# SCH_SpotiFi_2026-06-15.net
KiCad netlist of a schematic drawn in EasyEDA
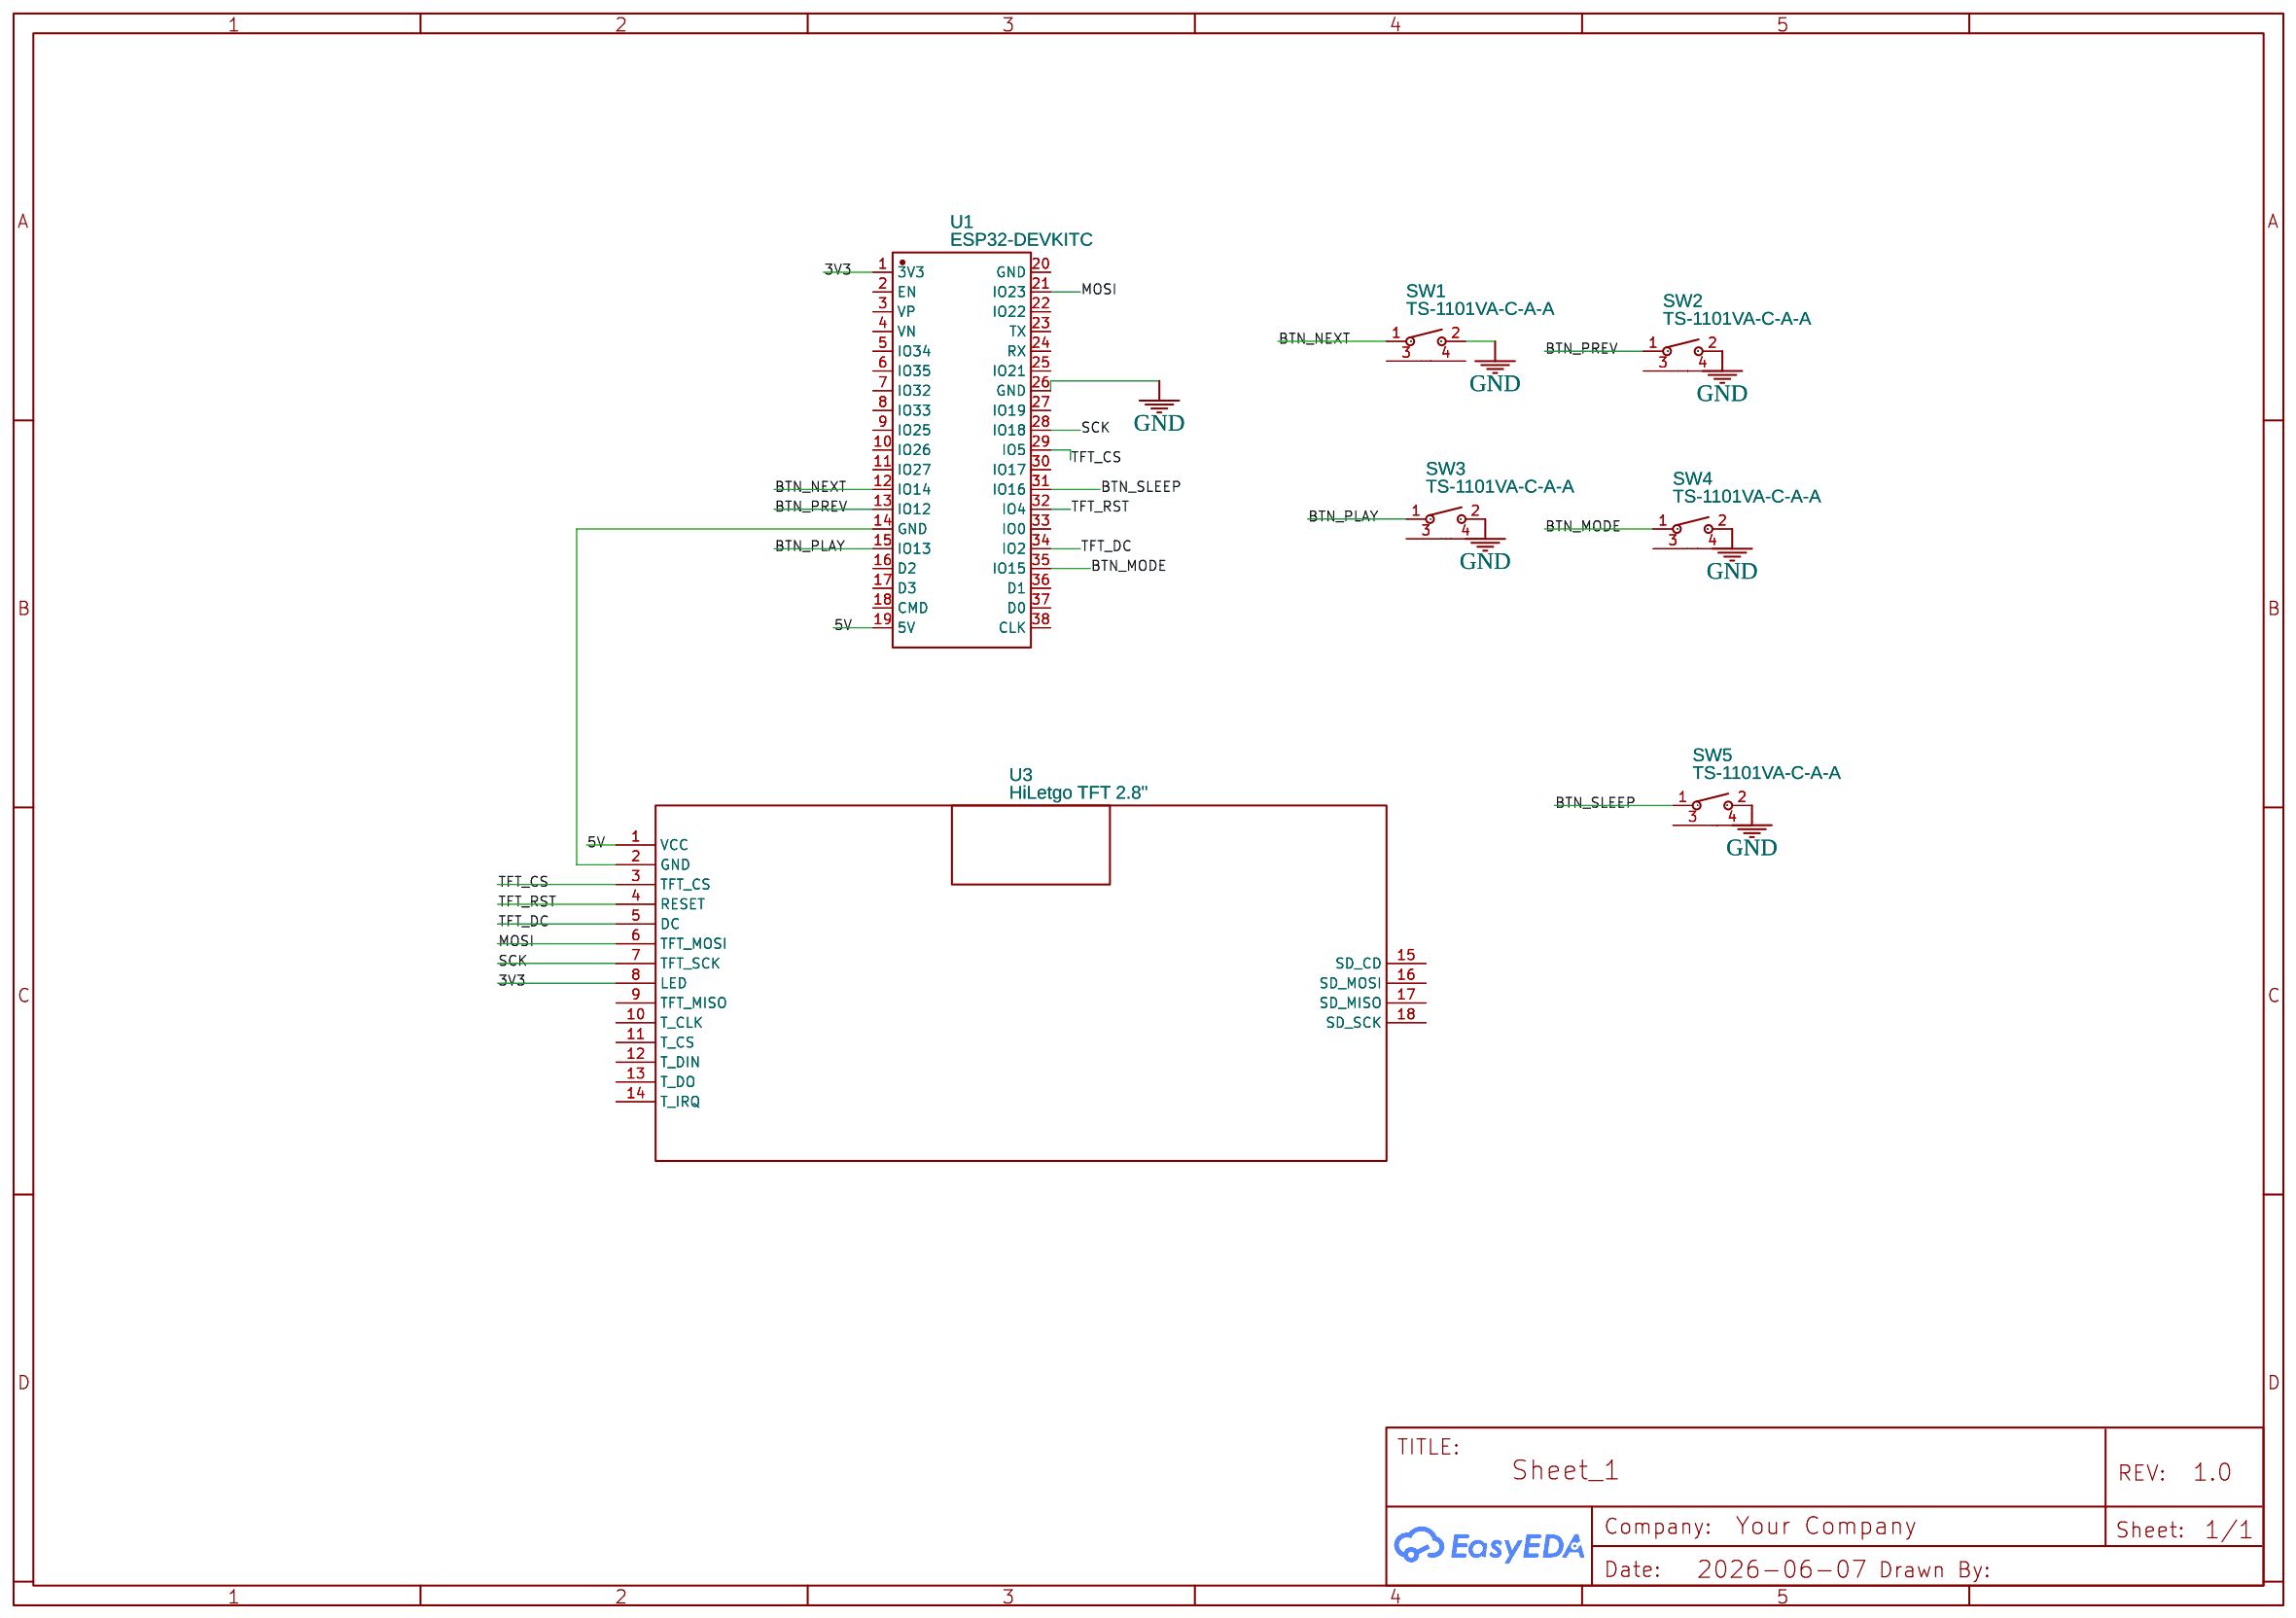
[diagram p0: schematic sheet]

(export (version "E")
  (design (tool "Eeschema 10.0.6"))
  (components
    (comp (ref "SW1")
      (value "TS-1101VA-C-A-A")
      (fields (field (name "Manufacturer") "XKB Connection(中国星坤)"))
      (libsource (lib "") (part "TS-1101VA-C-A-A"))
    )
    (comp (ref "SW2")
      (value "TS-1101VA-C-A-A")
      (fields (field (name "Manufacturer") "XKB Connection(中国星坤)"))
      (libsource (lib "") (part "TS-1101VA-C-A-A"))
    )
    (comp (ref "SW3")
      (value "TS-1101VA-C-A-A")
      (fields (field (name "Manufacturer") "XKB Connection(中国星坤)"))
      (libsource (lib "") (part "TS-1101VA-C-A-A"))
    )
    (comp (ref "SW4")
      (value "TS-1101VA-C-A-A")
      (fields (field (name "Manufacturer") "XKB Connection(中国星坤)"))
      (libsource (lib "") (part "TS-1101VA-C-A-A"))
    )
    (comp (ref "SW5")
      (value "TS-1101VA-C-A-A")
      (fields (field (name "Manufacturer") "XKB Connection(中国星坤)"))
      (libsource (lib "") (part "TS-1101VA-C-A-A"))
    )
    (comp (ref "U1")
      (value "ESP32-DEVKITC")
      (fields
        (field (name "Manufacturer Part") "ESP32-DevKitC")
        (field (name "Manufacturer") "ESPRESSIF(乐鑫)")
      )
      (libsource (lib "") (part "ESP32-DEVKITC"))
    )
    (comp (ref "U3") (value "HiLetgo TFT 2.8\"") (libsource (lib "") (part "HiLetgo TFT 2.8{dblquote}")))
  )
  (nets
    (net (code "1") (name "/3V3") (class "Default")
      (node (ref "U1") (pin "1") (pinfunction "3V3_1") (pintype "unspecified"))
      (node (ref "U3") (pin "8") (pinfunction "LED_8") (pintype "unspecified"))
    )
    (net (code "2") (name "/5V") (class "Default")
      (node (ref "U1") (pin "19") (pinfunction "5V_19") (pintype "unspecified"))
      (node (ref "U3") (pin "1") (pinfunction "VCC_1") (pintype "unspecified"))
    )
    (net (code "3") (name "/BTN_MODE") (class "Default")
      (node (ref "SW4") (pin "1") (pinfunction "1_1") (pintype "unspecified"))
      (node (ref "U1") (pin "35") (pinfunction "IO15_35") (pintype "unspecified"))
    )
    (net (code "4") (name "/BTN_NEXT") (class "Default")
      (node (ref "SW1") (pin "1") (pinfunction "1_1") (pintype "unspecified"))
      (node (ref "U1") (pin "12") (pinfunction "IO14_12") (pintype "unspecified"))
    )
    (net (code "5") (name "/BTN_PLAY") (class "Default")
      (node (ref "SW3") (pin "1") (pinfunction "1_1") (pintype "unspecified"))
      (node (ref "U1") (pin "15") (pinfunction "IO13_15") (pintype "unspecified"))
    )
    (net (code "6") (name "/BTN_PREV") (class "Default")
      (node (ref "SW2") (pin "1") (pinfunction "1_1") (pintype "unspecified"))
      (node (ref "U1") (pin "13") (pinfunction "IO12_13") (pintype "unspecified"))
    )
    (net (code "7") (name "/BTN_SLEEP") (class "Default")
      (node (ref "SW5") (pin "1") (pinfunction "1_1") (pintype "unspecified"))
      (node (ref "U1") (pin "31") (pinfunction "IO16_31") (pintype "unspecified"))
    )
    (net (code "8") (name "/MOSI") (class "Default")
      (node (ref "U1") (pin "21") (pinfunction "IO23_21") (pintype "unspecified"))
      (node (ref "U3") (pin "6") (pinfunction "TFT_MOSI_6") (pintype "unspecified"))
    )
    (net (code "9") (name "/SCK") (class "Default")
      (node (ref "U1") (pin "28") (pinfunction "IO18_28") (pintype "unspecified"))
      (node (ref "U3") (pin "7") (pinfunction "TFT_SCK_7") (pintype "unspecified"))
    )
    (net (code "10") (name "/TFT_CS") (class "Default")
      (node (ref "U1") (pin "29") (pinfunction "IO5_29") (pintype "unspecified"))
      (node (ref "U3") (pin "3") (pinfunction "TFT_CS_3") (pintype "unspecified"))
    )
    (net (code "11") (name "/TFT_DC") (class "Default")
      (node (ref "U1") (pin "34") (pinfunction "IO2_34") (pintype "unspecified"))
      (node (ref "U3") (pin "5") (pinfunction "DC_5") (pintype "unspecified"))
    )
    (net (code "12") (name "/TFT_RST") (class "Default")
      (node (ref "U1") (pin "32") (pinfunction "IO4_32") (pintype "unspecified"))
      (node (ref "U3") (pin "4") (pinfunction "RESET_4") (pintype "unspecified"))
    )
    (net (code "13") (name "GND") (class "Default")
      (node (ref "SW1") (pin "2") (pinfunction "2_2") (pintype "unspecified"))
      (node (ref "SW2") (pin "2") (pinfunction "2_2") (pintype "unspecified"))
      (node (ref "SW3") (pin "2") (pinfunction "2_2") (pintype "unspecified"))
      (node (ref "SW4") (pin "2") (pinfunction "2_2") (pintype "unspecified"))
      (node (ref "SW5") (pin "2") (pinfunction "2_2") (pintype "unspecified"))
      (node (ref "U1") (pin "26") (pinfunction "GND_26") (pintype "unspecified"))
    )
    (net (code "14") (name "Net-(U3-GND)") (class "Default")
      (node (ref "U1") (pin "14") (pinfunction "GND_14") (pintype "unspecified"))
      (node (ref "U3") (pin "2") (pinfunction "GND_2") (pintype "unspecified"))
    )
    (net (code "15") (name "unconnected-(SW1-Pad3)") (class "Default")
      (node (ref "SW1") (pin "3") (pinfunction "3_3") (pintype "unspecified"))
    )
    (net (code "16") (name "unconnected-(SW1-Pad4)") (class "Default")
      (node (ref "SW1") (pin "4") (pinfunction "4_4") (pintype "unspecified"))
    )
    (net (code "17") (name "unconnected-(SW2-Pad3)") (class "Default")
      (node (ref "SW2") (pin "3") (pinfunction "3_3") (pintype "unspecified"))
    )
    (net (code "18") (name "unconnected-(SW2-Pad4)") (class "Default")
      (node (ref "SW2") (pin "4") (pinfunction "4_4") (pintype "unspecified"))
    )
    (net (code "19") (name "unconnected-(SW3-Pad3)") (class "Default")
      (node (ref "SW3") (pin "3") (pinfunction "3_3") (pintype "unspecified"))
    )
    (net (code "20") (name "unconnected-(SW3-Pad4)") (class "Default")
      (node (ref "SW3") (pin "4") (pinfunction "4_4") (pintype "unspecified"))
    )
    (net (code "21") (name "unconnected-(SW4-Pad3)") (class "Default")
      (node (ref "SW4") (pin "3") (pinfunction "3_3") (pintype "unspecified"))
    )
    (net (code "22") (name "unconnected-(SW4-Pad4)") (class "Default")
      (node (ref "SW4") (pin "4") (pinfunction "4_4") (pintype "unspecified"))
    )
    (net (code "23") (name "unconnected-(SW5-Pad3)") (class "Default")
      (node (ref "SW5") (pin "3") (pinfunction "3_3") (pintype "unspecified"))
    )
    (net (code "24") (name "unconnected-(SW5-Pad4)") (class "Default")
      (node (ref "SW5") (pin "4") (pinfunction "4_4") (pintype "unspecified"))
    )
    (net (code "25") (name "unconnected-(U1-CLK-Pad38)") (class "Default")
      (node (ref "U1") (pin "38") (pinfunction "CLK_38") (pintype "unspecified"))
    )
    (net (code "26") (name "unconnected-(U1-CMD-Pad18)") (class "Default")
      (node (ref "U1") (pin "18") (pinfunction "CMD_18") (pintype "unspecified"))
    )
    (net (code "27") (name "unconnected-(U1-D0-Pad37)") (class "Default")
      (node (ref "U1") (pin "37") (pinfunction "D0_37") (pintype "unspecified"))
    )
    (net (code "28") (name "unconnected-(U1-D1-Pad36)") (class "Default")
      (node (ref "U1") (pin "36") (pinfunction "D1_36") (pintype "unspecified"))
    )
    (net (code "29") (name "unconnected-(U1-D2-Pad16)") (class "Default")
      (node (ref "U1") (pin "16") (pinfunction "D2_16") (pintype "unspecified"))
    )
    (net (code "30") (name "unconnected-(U1-D3-Pad17)") (class "Default")
      (node (ref "U1") (pin "17") (pinfunction "D3_17") (pintype "unspecified"))
    )
    (net (code "31") (name "unconnected-(U1-EN-Pad2)") (class "Default")
      (node (ref "U1") (pin "2") (pinfunction "EN_2") (pintype "unspecified"))
    )
    (net (code "32") (name "unconnected-(U1-GND-Pad20)") (class "Default")
      (node (ref "U1") (pin "20") (pinfunction "GND_20") (pintype "unspecified"))
    )
    (net (code "33") (name "unconnected-(U1-IO0-Pad33)") (class "Default")
      (node (ref "U1") (pin "33") (pinfunction "IO0_33") (pintype "unspecified"))
    )
    (net (code "34") (name "unconnected-(U1-IO17-Pad30)") (class "Default")
      (node (ref "U1") (pin "30") (pinfunction "IO17_30") (pintype "unspecified"))
    )
    (net (code "35") (name "unconnected-(U1-IO19-Pad27)") (class "Default")
      (node (ref "U1") (pin "27") (pinfunction "IO19_27") (pintype "unspecified"))
    )
    (net (code "36") (name "unconnected-(U1-IO21-Pad25)") (class "Default")
      (node (ref "U1") (pin "25") (pinfunction "IO21_25") (pintype "unspecified"))
    )
    (net (code "37") (name "unconnected-(U1-IO22-Pad22)") (class "Default")
      (node (ref "U1") (pin "22") (pinfunction "IO22_22") (pintype "unspecified"))
    )
    (net (code "38") (name "unconnected-(U1-IO25-Pad9)") (class "Default")
      (node (ref "U1") (pin "9") (pinfunction "IO25_9") (pintype "unspecified"))
    )
    (net (code "39") (name "unconnected-(U1-IO26-Pad10)") (class "Default")
      (node (ref "U1") (pin "10") (pinfunction "IO26_10") (pintype "unspecified"))
    )
    (net (code "40") (name "unconnected-(U1-IO27-Pad11)") (class "Default")
      (node (ref "U1") (pin "11") (pinfunction "IO27_11") (pintype "unspecified"))
    )
    (net (code "41") (name "unconnected-(U1-IO32-Pad7)") (class "Default")
      (node (ref "U1") (pin "7") (pinfunction "IO32_7") (pintype "unspecified"))
    )
    (net (code "42") (name "unconnected-(U1-IO33-Pad8)") (class "Default")
      (node (ref "U1") (pin "8") (pinfunction "IO33_8") (pintype "unspecified"))
    )
    (net (code "43") (name "unconnected-(U1-IO34-Pad5)") (class "Default")
      (node (ref "U1") (pin "5") (pinfunction "IO34_5") (pintype "unspecified"))
    )
    (net (code "44") (name "unconnected-(U1-IO35-Pad6)") (class "Default")
      (node (ref "U1") (pin "6") (pinfunction "IO35_6") (pintype "unspecified"))
    )
    (net (code "45") (name "unconnected-(U1-RX-Pad24)") (class "Default")
      (node (ref "U1") (pin "24") (pinfunction "RX_24") (pintype "unspecified"))
    )
    (net (code "46") (name "unconnected-(U1-TX-Pad23)") (class "Default")
      (node (ref "U1") (pin "23") (pinfunction "TX_23") (pintype "unspecified"))
    )
    (net (code "47") (name "unconnected-(U1-VN-Pad4)") (class "Default")
      (node (ref "U1") (pin "4") (pinfunction "VN_4") (pintype "unspecified"))
    )
    (net (code "48") (name "unconnected-(U1-VP-Pad3)") (class "Default")
      (node (ref "U1") (pin "3") (pinfunction "VP_3") (pintype "unspecified"))
    )
    (net (code "49") (name "unconnected-(U3-SD_CD-Pad15)") (class "Default")
      (node (ref "U3") (pin "15") (pinfunction "SD_CD_15") (pintype "unspecified"))
    )
    (net (code "50") (name "unconnected-(U3-SD_MISO-Pad17)") (class "Default")
      (node (ref "U3") (pin "17") (pinfunction "SD_MISO_17") (pintype "unspecified"))
    )
    (net (code "51") (name "unconnected-(U3-SD_MOSI-Pad16)") (class "Default")
      (node (ref "U3") (pin "16") (pinfunction "SD_MOSI_16") (pintype "unspecified"))
    )
    (net (code "52") (name "unconnected-(U3-SD_SCK-Pad18)") (class "Default")
      (node (ref "U3") (pin "18") (pinfunction "SD_SCK_18") (pintype "unspecified"))
    )
    (net (code "53") (name "unconnected-(U3-TFT_MISO-Pad9)") (class "Default")
      (node (ref "U3") (pin "9") (pinfunction "TFT_MISO_9") (pintype "unspecified"))
    )
    (net (code "54") (name "unconnected-(U3-T_CLK-Pad10)") (class "Default")
      (node (ref "U3") (pin "10") (pinfunction "T_CLK_10") (pintype "unspecified"))
    )
    (net (code "55") (name "unconnected-(U3-T_CS-Pad11)") (class "Default")
      (node (ref "U3") (pin "11") (pinfunction "T_CS_11") (pintype "unspecified"))
    )
    (net (code "56") (name "unconnected-(U3-T_DIN-Pad12)") (class "Default")
      (node (ref "U3") (pin "12") (pinfunction "T_DIN_12") (pintype "unspecified"))
    )
    (net (code "57") (name "unconnected-(U3-T_DO-Pad13)") (class "Default")
      (node (ref "U3") (pin "13") (pinfunction "T_DO_13") (pintype "unspecified"))
    )
    (net (code "58") (name "unconnected-(U3-T_IRQ-Pad14)") (class "Default")
      (node (ref "U3") (pin "14") (pinfunction "T_IRQ_14") (pintype "unspecified"))
    )
  )
)
